# QCopterFC_POWER_Sch.net
KiCad netlist of a schematic drawn in Altium Designer
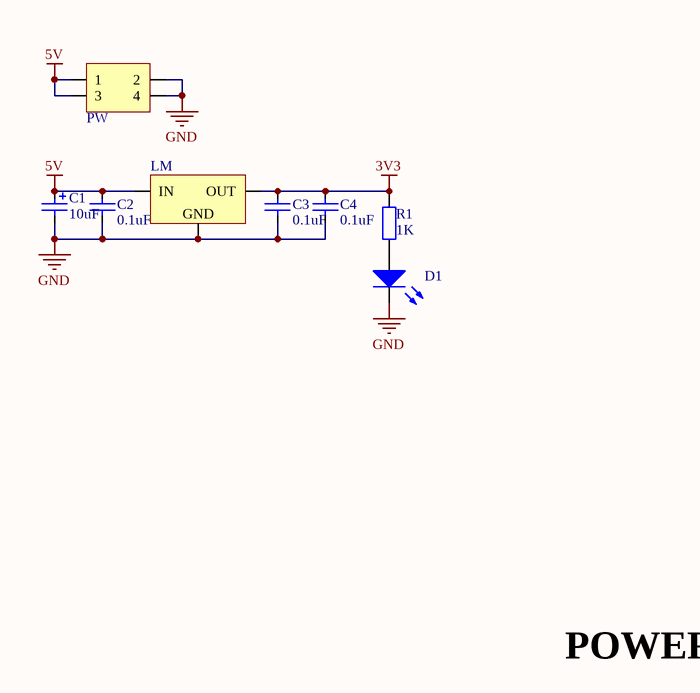
[diagram p0: QCopterFC_POWER_Sch.SchDoc]

(export (version "E")
  (design (tool "Eeschema 10.0.6"))
  (components
    (comp (ref "C1")
      (value "10uF")
      (footprint "PCB_Passive:CAP_TAN_B1210")
      (description "Capacitor")
      (fields (field (name "Comment") "Cap_Tan_1210"))
      (libsource (lib "SCH_Passive") (part "Cap_Tan_1210"))
    )
    (comp (ref "C2")
      (value "0.1uF")
      (footprint "PCB_Passive:CAP_0603")
      (description "Capacitor")
      (fields (field (name "Comment") "Cap_0603"))
      (libsource (lib "SCH_Passive") (part "Cap_0603"))
    )
    (comp (ref "C3")
      (value "0.1uF")
      (footprint "PCB_Passive:CAP_0603")
      (description "Capacitor")
      (fields (field (name "Comment") "Cap_0603"))
      (libsource (lib "SCH_Passive") (part "Cap_0603"))
    )
    (comp (ref "C4")
      (value "0.1uF")
      (footprint "PCB_Passive:CAP_0603")
      (description "Capacitor")
      (fields (field (name "Comment") "Cap_0603"))
      (libsource (lib "SCH_Passive") (part "Cap_0603"))
    )
    (comp (ref "D1")
      (value "LED_0603_BLUE")
      (footprint "PCB_Active:LED_0603_WHITE")
      (description "LED")
      (libsource (lib "SCH_Active") (part "LED_0603_BLUE"))
    )
    (comp (ref "LM")
      (value "LM1117")
      (footprint "PCB_IC:SOT223")
      (description "Power")
      (libsource (lib "SCH_IC") (part "LM1117"))
    )
    (comp (ref "PW")
      (value "HDR2X2_90_2.54")
      (footprint "PCB_Connector:HDR2X2_90_2.54")
      (description "Header")
      (libsource (lib "SCH_Connector") (part "HDR2X2_90_2.54"))
    )
    (comp (ref "R1")
      (value "1K")
      (footprint "PCB_Passive:RES_0603")
      (description "Resistor")
      (fields (field (name "Comment") "Res_0603"))
      (libsource (lib "SCH_Passive") (part "Res_0603"))
    )
  )
  (nets
    (net (code "1") (name "3V3") (class "Default")
      (node (ref "C3") (pin "2") (pinfunction "2_2") (pintype "passive"))
      (node (ref "C4") (pin "2") (pinfunction "2_2") (pintype "passive"))
      (node (ref "LM") (pin "2") (pinfunction "OUT_2") (pintype "power_in"))
      (node (ref "R1") (pin "2") (pinfunction "2_2") (pintype "passive"))
    )
    (net (code "2") (name "5V") (class "Default")
      (node (ref "C1") (pin "1") (pinfunction "1_1") (pintype "passive"))
      (node (ref "C2") (pin "2") (pinfunction "2_2") (pintype "passive"))
      (node (ref "LM") (pin "3") (pinfunction "IN_3") (pintype "power_in"))
      (node (ref "PW") (pin "1") (pinfunction "1_1") (pintype "passive"))
      (node (ref "PW") (pin "3") (pinfunction "3_3") (pintype "passive"))
    )
    (net (code "3") (name "GND") (class "Default")
      (node (ref "C1") (pin "2") (pinfunction "2_2") (pintype "passive"))
      (node (ref "C2") (pin "1") (pinfunction "1_1") (pintype "passive"))
      (node (ref "C3") (pin "1") (pinfunction "1_1") (pintype "passive"))
      (node (ref "C4") (pin "1") (pinfunction "1_1") (pintype "passive"))
      (node (ref "D1") (pin "2") (pinfunction "K_2") (pintype "passive"))
      (node (ref "LM") (pin "1") (pinfunction "GND_1") (pintype "power_in"))
      (node (ref "PW") (pin "2") (pinfunction "2_2") (pintype "passive"))
      (node (ref "PW") (pin "4") (pinfunction "4_4") (pintype "passive"))
    )
    (net (code "4") (name "Net-(D1-A)") (class "Default")
      (node (ref "D1") (pin "1") (pinfunction "A_1") (pintype "passive"))
      (node (ref "R1") (pin "1") (pinfunction "1_1") (pintype "passive"))
    )
  )
)
